# power.net
KiCad netlist of a schematic drawn in Altium Designer
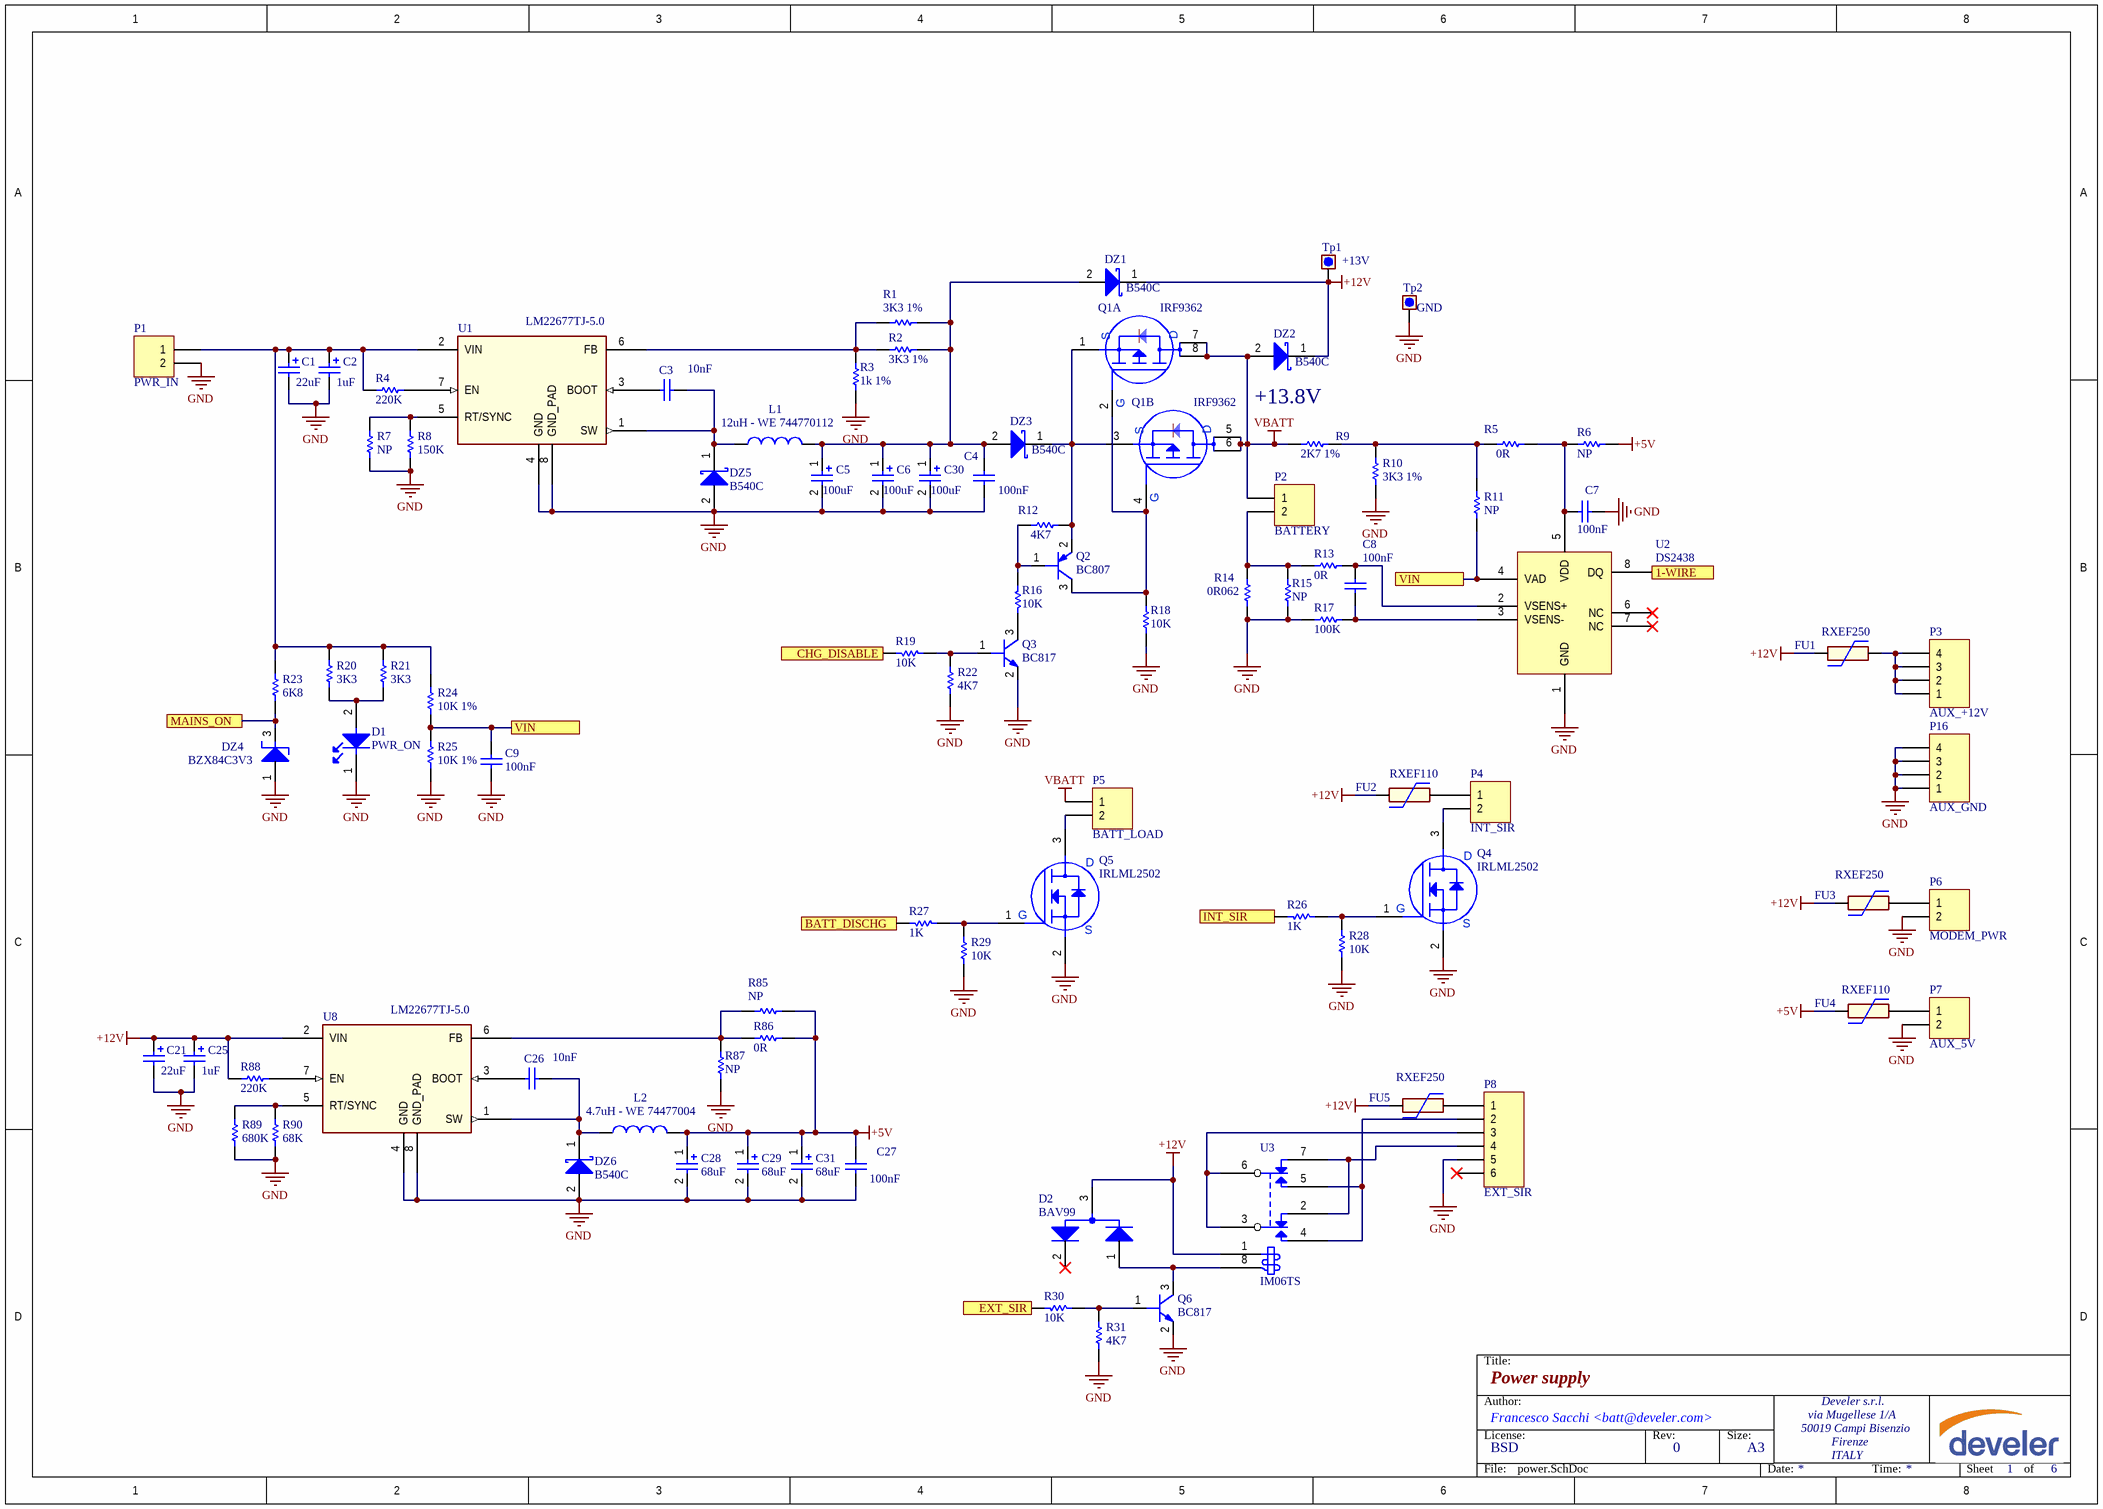
[diagram p0: power.SchDoc]

(export (version "E")
  (design (tool "Eeschema 10.0.6"))
  (components
    (comp (ref "C1")
      (value "22uF")
      (footprint "1206_[3216]")
      (description "Ceramic X7R 50V")
      (fields (field (name "PUBLISHER") "Altium Limited"))
      (libsource (lib "DEVELER_Library") (part "Cap Pol1"))
    )
    (comp (ref "C2")
      (value "1uF")
      (footprint "1206_[3216]")
      (description "Ceramic X7R 50V")
      (fields (field (name "PUBLISHER") "Altium Limited"))
      (libsource (lib "DEVELER_Library") (part "Cap Pol1"))
    )
    (comp (ref "C3")
      (value "10nF")
      (footprint "0603_[1608]")
      (description "Ceramic X7R 50V")
      (fields (field (name "PUBLISHER") "Altium Limited"))
      (libsource (lib "Miscellaneous Devices") (part "Cap"))
    )
    (comp (ref "C4")
      (value "100nF")
      (footprint "0603_[1608]")
      (description "Ceramic X7R 50V")
      (fields (field (name "PUBLISHER") "Altium Limited"))
      (libsource (lib "DEVELER_Library") (part "Cap"))
    )
    (comp (ref "C5")
      (value "100uF")
      (footprint "[7343]_CAP_TAN")
      (description "Tantalum 25V T491X107K025AT")
      (fields (field (name "PUBLISHER") "Altium Limited"))
      (libsource (lib "") (part "Cap Pol1_1"))
    )
    (comp (ref "C6")
      (value "100uF")
      (footprint "[7343]_CAP_TAN")
      (description "Tantalum 25V T491X107K025AT")
      (fields (field (name "PUBLISHER") "Altium Limited"))
      (libsource (lib "") (part "Cap Pol1_1"))
    )
    (comp (ref "C7")
      (value "100nF")
      (footprint "0603_[1608]")
      (description "Ceramic X7R 50V")
      (fields (field (name "PUBLISHER") "Altium Limited"))
      (libsource (lib "DEVELER_Library") (part "Cap"))
    )
    (comp (ref "C8")
      (value "100nF")
      (footprint "0603_[1608]")
      (description "Ceramic X7R 50V")
      (fields (field (name "PUBLISHER") "Altium Limited"))
      (libsource (lib "DEVELER_Library") (part "Cap"))
    )
    (comp (ref "C9")
      (value "100nF")
      (footprint "0603_[1608]")
      (description "Ceramic X7R 50V")
      (fields (field (name "PUBLISHER") "Altium Limited"))
      (libsource (lib "DEVELER_Library") (part "Cap"))
    )
    (comp (ref "C21")
      (value "22uF")
      (footprint "1206_[3216]")
      (description "Ceramic X7R 50V")
      (fields (field (name "PUBLISHER") "Altium Limited"))
      (libsource (lib "DEVELER_Library") (part "Cap Pol1"))
    )
    (comp (ref "C25")
      (value "1uF")
      (footprint "1206_[3216]")
      (description "Ceramic X7R 50V")
      (fields (field (name "PUBLISHER") "Altium Limited"))
      (libsource (lib "DEVELER_Library") (part "Cap Pol1"))
    )
    (comp (ref "C26")
      (value "10nF")
      (footprint "0603_[1608]")
      (description "Ceramic X7R 50V")
      (fields (field (name "PUBLISHER") "Altium Limited"))
      (libsource (lib "Miscellaneous Devices") (part "Cap"))
    )
    (comp (ref "C27")
      (value "100nF")
      (footprint "0603_[1608]")
      (description "Ceramic X7R 50V")
      (fields (field (name "PUBLISHER") "Altium Limited"))
      (libsource (lib "DEVELER_Library") (part "Cap"))
    )
    (comp (ref "C28")
      (value "68uF")
      (footprint "[7343]_CAP_TAN")
      (description "Tantalum 25V T491X107K025AT")
      (fields (field (name "PUBLISHER") "Altium Limited"))
      (libsource (lib "") (part "Cap Pol1_1"))
    )
    (comp (ref "C29")
      (value "68uF")
      (footprint "[7343]_CAP_TAN")
      (description "Tantalum 25V T491X107K025AT")
      (fields (field (name "PUBLISHER") "Altium Limited"))
      (libsource (lib "") (part "Cap Pol1_1"))
    )
    (comp (ref "C30")
      (value "100uF")
      (footprint "[7343]_CAP_TAN")
      (description "Tantalum 25V T491X107K025AT")
      (fields (field (name "PUBLISHER") "Altium Limited"))
      (libsource (lib "") (part "Cap Pol1_1"))
    )
    (comp (ref "C31")
      (value "68uF")
      (footprint "[7343]_CAP_TAN")
      (description "Tantalum 25V T491X107K025AT")
      (fields (field (name "PUBLISHER") "Altium Limited"))
      (libsource (lib "") (part "Cap Pol1_1"))
    )
    (comp (ref "D1")
      (value "PWR_ON")
      (footprint "0805_[2012]_LED")
      (description "Multicolor LED")
      (libsource (lib "DEVELER_Library") (part "LED"))
    )
    (comp (ref "D2")
      (value "BAV99")
      (footprint "SOT-23")
      (description "SOT23")
      (libsource (lib "DEVELER_Library") (part "BAV99"))
    )
    (comp (ref "DZ1")
      (value "B540C")
      (footprint "DO214AB_K1-A2_SMC")
      (description "Diode Schottky (SSC54)")
      (fields (field (name "PUBLISHER") "Altium Limited"))
      (libsource (lib "Miscellaneous Devices") (part "D Schottky"))
    )
    (comp (ref "DZ2")
      (value "B540C")
      (footprint "DO214AB_K1-A2_SMC")
      (description "Diode Schottky (SSC54)")
      (fields (field (name "PUBLISHER") "Altium Limited"))
      (libsource (lib "Miscellaneous Devices") (part "D Schottky"))
    )
    (comp (ref "DZ3")
      (value "B540C")
      (footprint "DO214AB_K1-A2_SMC")
      (description "Diode Schottky (SSC54)")
      (fields (field (name "PUBLISHER") "Altium Limited"))
      (libsource (lib "Miscellaneous Devices") (part "D Schottky"))
    )
    (comp (ref "DZ4")
      (value "BZX84C3V3")
      (footprint "SOT-23_L")
      (description "Zener 0.35W")
      (libsource (lib "DEVELER_Library") (part "ZENER_BZX"))
    )
    (comp (ref "DZ5")
      (value "B540C")
      (footprint "DO214AB_K1-A2_SMC")
      (description "Diode Schottky (SSC54)")
      (fields (field (name "PUBLISHER") "Altium Limited"))
      (libsource (lib "Miscellaneous Devices") (part "D Schottky"))
    )
    (comp (ref "DZ6")
      (value "B540C")
      (footprint "DO214AB_K1-A2_SMC")
      (description "Diode Schottky (SSC54)")
      (fields (field (name "PUBLISHER") "Altium Limited"))
      (libsource (lib "Miscellaneous Devices") (part "D Schottky"))
    )
    (comp (ref "FU1")
      (value "RXEF250")
      (footprint "RADIAL-10.2mm-polyswitch")
      (description "Fuse autoreset")
      (libsource (lib "DEVELER_Library") (part "FuseAutoReset"))
    )
    (comp (ref "FU2")
      (value "RXEF110")
      (footprint "RADIAL_5.08mm_polyswitch")
      (description "Fuse autoreset")
      (libsource (lib "DEVELER_Library") (part "FuseAutoReset"))
    )
    (comp (ref "FU3")
      (value "RXEF250")
      (footprint "RADIAL-10.2mm-polyswitch")
      (description "Fuse autoreset")
      (libsource (lib "DEVELER_Library") (part "FuseAutoReset"))
    )
    (comp (ref "FU4")
      (value "RXEF110")
      (footprint "RADIAL_5.08mm_polyswitch")
      (description "Fuse autoreset")
      (libsource (lib "DEVELER_Library") (part "FuseAutoReset"))
    )
    (comp (ref "FU5")
      (value "RXEF250")
      (footprint "RADIAL-10.2mm-polyswitch")
      (description "Fuse autoreset")
      (libsource (lib "DEVELER_Library") (part "FuseAutoReset"))
    )
    (comp (ref "L1")
      (value "12uH - WE 744770112")
      (footprint "WE-PD_1280")
      (description "SMD Shielded Tiny Power Inductor")
      (fields (field (name "PUBLISHER") "Altium Limited"))
      (libsource (lib "Miscellaneous Devices") (part "Inductor"))
    )
    (comp (ref "L2")
      (value "4.7uH - WE 74477004")
      (footprint "WE-PD_1280")
      (description "SMD Shielded Tiny Power Inductor")
      (fields (field (name "PUBLISHER") "Altium Limited"))
      (libsource (lib "Miscellaneous Devices") (part "Inductor"))
    )
    (comp (ref "P1")
      (value "PWR_IN")
      (footprint "TBLOCK_1X2_3.5MM_HOR_THD")
      (description "Header, 2-Pin")
      (fields (field (name "PUBLISHER") "Altium Limited"))
      (libsource (lib "") (part "Header 2_1"))
    )
    (comp (ref "P2")
      (value "BATTERY")
      (footprint "TBLOCK_1X2_3.5MM_HOR_THD")
      (description "Header, 2-Pin")
      (fields (field (name "PUBLISHER") "Altium Limited"))
      (libsource (lib "Miscellaneous Connectors") (part "Header 2"))
    )
    (comp (ref "P3")
      (value "AUX_+12V")
      (footprint "TBLOCK_1X4_3.5MM_HOR_THD")
      (description "Header, 4-Pin")
      (fields (field (name "PUBLISHER") "Altium Limited"))
      (libsource (lib "Miscellaneous Connectors") (part "Header 4"))
    )
    (comp (ref "P4")
      (value "INT_SIR")
      (footprint "TBLOCK_1X2_3.5MM_HOR_THD")
      (description "Header, 2-Pin")
      (fields (field (name "PUBLISHER") "Altium Limited"))
      (libsource (lib "Miscellaneous Connectors") (part "Header 2"))
    )
    (comp (ref "P5")
      (value "BATT_LOAD")
      (footprint "TBLOCK_1X2_3.5MM_HOR_THD")
      (description "Header, 2-Pin")
      (fields (field (name "PUBLISHER") "Altium Limited"))
      (libsource (lib "Miscellaneous Connectors") (part "Header 2"))
    )
    (comp (ref "P6")
      (value "MODEM_PWR")
      (footprint "TBLOCK_1X2_3.5MM_HOR_THD")
      (description "Header, 2-Pin")
      (fields (field (name "PUBLISHER") "Altium Limited"))
      (libsource (lib "Miscellaneous Connectors") (part "Header 2"))
    )
    (comp (ref "P7")
      (value "AUX_5V")
      (footprint "TBLOCK_1X2_3.5MM_HOR_THD")
      (description "Header, 2-Pin")
      (fields (field (name "PUBLISHER") "Altium Limited"))
      (libsource (lib "Miscellaneous Connectors") (part "Header 2"))
    )
    (comp (ref "P8")
      (value "EXT_SIR")
      (footprint "TBLOCK_1X6_3.5MM_HOR_THD")
      (description "Header, 6-Pin")
      (fields (field (name "PUBLISHER") "Altium Limited"))
      (libsource (lib "Miscellaneous Connectors") (part "Header 6"))
    )
    (comp (ref "P16")
      (value "AUX_GND")
      (footprint "TBLOCK_1X4_3.5MM_HOR_THD")
      (description "Header, 4-Pin")
      (fields (field (name "PUBLISHER") "Altium Limited"))
      (libsource (lib "Miscellaneous Connectors") (part "Header 4"))
    )
    (comp (ref "Q1")
      (value "IRF9362")
      (footprint "SOIC8")
      (description "Dual channel P-MOS in same package")
      (libsource (lib "DEVELER_Library") (part "MOSFET-P dual"))
    )
    (comp (ref "Q2")
      (value "BC807")
      (footprint "SOT-23")
      (description "PNP Trasistor")
      (libsource (lib "DEVELER_Library") (part "BC807"))
    )
    (comp (ref "Q3")
      (value "BC817")
      (footprint "SOT-23")
      (description "NPN Transistor")
      (libsource (lib "DEVELER_Library") (part "BC817"))
    )
    (comp (ref "Q4")
      (value "IRLML2502")
      (footprint "sot-23")
      (description "N MOS")
      (libsource (lib "DEVELER_Library") (part "MOSFET-N 3pin"))
    )
    (comp (ref "Q5")
      (value "IRLML2502")
      (footprint "sot-23")
      (description "N MOS")
      (libsource (lib "DEVELER_Library") (part "MOSFET-N 3pin"))
    )
    (comp (ref "Q6")
      (value "BC817")
      (footprint "SOT-23")
      (description "NPN Transistor")
      (libsource (lib "DEVELER_Library") (part "BC817"))
    )
    (comp (ref "R1")
      (value "3K3 1%")
      (footprint "0603_[1608]")
      (description "Resistor")
      (libsource (lib "DEVELER_Library") (part "Res1"))
    )
    (comp (ref "R2")
      (value "3K3 1%")
      (footprint "0603_[1608]")
      (description "Resistor")
      (libsource (lib "DEVELER_Library") (part "Res1"))
    )
    (comp (ref "R3")
      (value "1k 1%")
      (footprint "0603_[1608]")
      (description "Resistor")
      (libsource (lib "DEVELER_Library") (part "Res1"))
    )
    (comp (ref "R4")
      (value "220K")
      (footprint "0603_[1608]")
      (description "Resistor")
      (libsource (lib "DEVELER_Library") (part "Res1"))
    )
    (comp (ref "R5")
      (value "0R")
      (footprint "0603_[1608]")
      (description "Resistor")
      (libsource (lib "DEVELER_Library") (part "Res1"))
    )
    (comp (ref "R6")
      (value "NP")
      (footprint "0603_[1608]")
      (description "Resistor")
      (libsource (lib "DEVELER_Library") (part "Res1"))
    )
    (comp (ref "R7")
      (value "NP")
      (footprint "0603_[1608]")
      (description "Resistor")
      (libsource (lib "DEVELER_Library") (part "Res1"))
    )
    (comp (ref "R8")
      (value "150K")
      (footprint "0603_[1608]")
      (description "Resistor")
      (libsource (lib "DEVELER_Library") (part "Res1"))
    )
    (comp (ref "R9")
      (value "2K7 1%")
      (footprint "0603_[1608]")
      (description "Resistor")
      (libsource (lib "DEVELER_Library") (part "Res1"))
    )
    (comp (ref "R10")
      (value "3K3 1%")
      (footprint "0603_[1608]")
      (description "Resistor")
      (libsource (lib "DEVELER_Library") (part "Res1"))
    )
    (comp (ref "R11")
      (value "NP")
      (footprint "0603_[1608]")
      (description "Resistor")
      (libsource (lib "DEVELER_Library") (part "Res1"))
    )
    (comp (ref "R12")
      (value "4K7")
      (footprint "0603_[1608]")
      (description "Resistor")
      (libsource (lib "DEVELER_Library") (part "Res1"))
    )
    (comp (ref "R13")
      (value "0R")
      (footprint "0603_[1608]")
      (description "Resistor")
      (libsource (lib "DEVELER_Library") (part "Res1"))
    )
    (comp (ref "R14")
      (value "0R062")
      (footprint "1020_[2550]")
      (description "Resistor")
      (libsource (lib "DEVELER_Library") (part "Res1"))
    )
    (comp (ref "R15")
      (value "NP")
      (footprint "0603_[1608]")
      (description "Resistor")
      (libsource (lib "DEVELER_Library") (part "Res1"))
    )
    (comp (ref "R16")
      (value "10K")
      (footprint "0603_[1608]")
      (description "Resistor")
      (libsource (lib "DEVELER_Library") (part "Res1"))
    )
    (comp (ref "R17")
      (value "100K")
      (footprint "0603_[1608]")
      (description "Resistor")
      (libsource (lib "DEVELER_Library") (part "Res1"))
    )
    (comp (ref "R18")
      (value "10K")
      (footprint "0603_[1608]")
      (description "Resistor")
      (libsource (lib "DEVELER_Library") (part "Res1"))
    )
    (comp (ref "R19")
      (value "10K")
      (footprint "0603_[1608]")
      (description "Resistor")
      (libsource (lib "DEVELER_Library") (part "Res1"))
    )
    (comp (ref "R20")
      (value "3K3")
      (footprint "0603_[1608]")
      (description "Resistor")
      (libsource (lib "DEVELER_Library") (part "Res1"))
    )
    (comp (ref "R21")
      (value "3K3")
      (footprint "0603_[1608]")
      (description "Resistor")
      (libsource (lib "DEVELER_Library") (part "Res1"))
    )
    (comp (ref "R22")
      (value "4K7")
      (footprint "0603_[1608]")
      (description "Resistor")
      (libsource (lib "DEVELER_Library") (part "Res1"))
    )
    (comp (ref "R23")
      (value "6K8")
      (footprint "0603_[1608]")
      (description "Resistor")
      (libsource (lib "DEVELER_Library") (part "Res1"))
    )
    (comp (ref "R24")
      (value "10K 1%")
      (footprint "0603_[1608]")
      (description "Resistor")
      (libsource (lib "DEVELER_Library") (part "Res1"))
    )
    (comp (ref "R25")
      (value "10K 1%")
      (footprint "0603_[1608]")
      (description "Resistor")
      (libsource (lib "DEVELER_Library") (part "Res1"))
    )
    (comp (ref "R26")
      (value "1K")
      (footprint "0603_[1608]")
      (description "Resistor")
      (libsource (lib "DEVELER_Library") (part "Res1"))
    )
    (comp (ref "R27")
      (value "1K")
      (footprint "0603_[1608]")
      (description "Resistor")
      (libsource (lib "DEVELER_Library") (part "Res1"))
    )
    (comp (ref "R28")
      (value "10K")
      (footprint "0603_[1608]")
      (description "Resistor")
      (libsource (lib "DEVELER_Library") (part "Res1"))
    )
    (comp (ref "R29")
      (value "10K")
      (footprint "0603_[1608]")
      (description "Resistor")
      (libsource (lib "DEVELER_Library") (part "Res1"))
    )
    (comp (ref "R30")
      (value "10K")
      (footprint "0603_[1608]")
      (description "Resistor")
      (libsource (lib "DEVELER_Library") (part "Res1"))
    )
    (comp (ref "R31")
      (value "4K7")
      (footprint "0603_[1608]")
      (description "Resistor")
      (libsource (lib "DEVELER_Library") (part "Res1"))
    )
    (comp (ref "R85")
      (value "NP")
      (footprint "0603_[1608]")
      (description "Resistor")
      (libsource (lib "DEVELER_Library") (part "Res1"))
    )
    (comp (ref "R86")
      (value "0R")
      (footprint "0603_[1608]")
      (description "Resistor")
      (libsource (lib "DEVELER_Library") (part "Res1"))
    )
    (comp (ref "R87")
      (value "NP")
      (footprint "0603_[1608]")
      (description "Resistor")
      (libsource (lib "DEVELER_Library") (part "Res1"))
    )
    (comp (ref "R88")
      (value "220K")
      (footprint "0603_[1608]")
      (description "Resistor")
      (libsource (lib "DEVELER_Library") (part "Res1"))
    )
    (comp (ref "R89")
      (value "680K")
      (footprint "0603_[1608]")
      (description "Resistor")
      (libsource (lib "DEVELER_Library") (part "Res1"))
    )
    (comp (ref "R90")
      (value "68K")
      (footprint "0603_[1608]")
      (description "Resistor")
      (libsource (lib "DEVELER_Library") (part "Res1"))
    )
    (comp (ref "Tp1")
      (value "+13V")
      (footprint "TEST_POINT_THD_D1.6MM")
      (libsource (lib "DEVELER_Library") (part "Test_point"))
    )
    (comp (ref "Tp2")
      (value "GND")
      (footprint "TEST_POINT_THD_D1.6MM")
      (libsource (lib "DEVELER_Library") (part "Test_point"))
    )
    (comp (ref "U1")
      (value "LM22677TJ-5.0")
      (footprint "TO-263-7")
      (description "Switching regulator.")
      (libsource (lib "DEVELER_Library") (part "LM22670TJ-ADJ"))
    )
    (comp (ref "U2")
      (value "DS2438")
      (footprint "SOIC8")
      (description "Smart Battery Monitor")
      (libsource (lib "DEVELER_Library") (part "DS2438"))
    )
    (comp (ref "U3")
      (value "IM06TS")
      (footprint "RELAYS_DPST_THD_6x10_3.2mm")
      (description "Relay DPST")
      (libsource (lib "DEVELER_Library") (part "RELAY DPST"))
    )
    (comp (ref "U8")
      (value "LM22677TJ-5.0")
      (footprint "TO-263-7")
      (description "Switching regulator.")
      (libsource (lib "DEVELER_Library") (part "LM22670TJ-ADJ"))
    )
  )
  (nets
    (net (code "1") (name "+5V") (class "Default")
      (node (ref "C27") (pin "2") (pinfunction "2_2") (pintype "passive"))
      (node (ref "C28") (pin "1") (pinfunction "1_1") (pintype "passive"))
      (node (ref "C29") (pin "1") (pinfunction "1_1") (pintype "passive"))
      (node (ref "C31") (pin "1") (pinfunction "1_1") (pintype "passive"))
      (node (ref "FU4") (pin "1") (pinfunction "1_1") (pintype "passive"))
      (node (ref "L2") (pin "2") (pinfunction "2_2") (pintype "passive"))
      (node (ref "R6") (pin "1") (pinfunction "1_1") (pintype "passive"))
      (node (ref "R85") (pin "1") (pinfunction "1_1") (pintype "passive"))
      (node (ref "R86") (pin "1") (pinfunction "1_1") (pintype "passive"))
    )
    (net (code "2") (name "+12V") (class "Default")
      (node (ref "C21") (pin "1") (pinfunction "1_1") (pintype "passive"))
      (node (ref "C25") (pin "1") (pinfunction "1_1") (pintype "passive"))
      (node (ref "D2") (pin "3") (pinfunction "3_3") (pintype "passive"))
      (node (ref "DZ1") (pin "1") (pinfunction "K_1") (pintype "passive"))
      (node (ref "DZ2") (pin "1") (pinfunction "K_1") (pintype "passive"))
      (node (ref "FU1") (pin "1") (pinfunction "1_1") (pintype "passive"))
      (node (ref "FU2") (pin "1") (pinfunction "1_1") (pintype "passive"))
      (node (ref "FU3") (pin "1") (pinfunction "1_1") (pintype "passive"))
      (node (ref "FU5") (pin "1") (pinfunction "1_1") (pintype "passive"))
      (node (ref "R88") (pin "1") (pinfunction "1_1") (pintype "passive"))
      (node (ref "Tp1") (pin "1") (pinfunction "1_1") (pintype "passive"))
      (node (ref "U3") (pin "1") (pinfunction "1_1") (pintype "passive"))
      (node (ref "U8") (pin "2") (pinfunction "VIN_2") (pintype "power_in"))
    )
    (net (code "3") (name "/1-WIRE") (class "Default")
      (node (ref "U2") (pin "8") (pinfunction "DQ_8") (pintype "passive"))
    )
    (net (code "4") (name "/BATT_DISCHG") (class "Default")
      (node (ref "R27") (pin "1") (pinfunction "1_1") (pintype "passive"))
    )
    (net (code "5") (name "/CHG_DISABLE") (class "Default")
      (node (ref "R19") (pin "1") (pinfunction "1_1") (pintype "passive"))
    )
    (net (code "6") (name "/EXT_SIR") (class "Default")
      (node (ref "R30") (pin "1") (pinfunction "1_1") (pintype "passive"))
    )
    (net (code "7") (name "/INT_SIR") (class "Default")
      (node (ref "R26") (pin "1") (pinfunction "1_1") (pintype "passive"))
    )
    (net (code "8") (name "/MAINS_ON") (class "Default")
      (node (ref "DZ4") (pin "3") (pinfunction "K_3") (pintype "passive"))
      (node (ref "R23") (pin "1") (pinfunction "1_1") (pintype "passive"))
    )
    (net (code "9") (name "/VIN") (class "Default")
      (node (ref "C9") (pin "2") (pinfunction "2_2") (pintype "passive"))
      (node (ref "R11") (pin "1") (pinfunction "1_1") (pintype "passive"))
      (node (ref "R24") (pin "1") (pinfunction "1_1") (pintype "passive"))
      (node (ref "R25") (pin "2") (pinfunction "2_2") (pintype "passive"))
      (node (ref "U2") (pin "4") (pinfunction "VAD_4") (pintype "passive"))
    )
    (net (code "10") (name "GND") (class "Default")
      (node (ref "C1") (pin "2") (pinfunction "2_2") (pintype "passive"))
      (node (ref "C2") (pin "2") (pinfunction "2_2") (pintype "passive"))
      (node (ref "C21") (pin "2") (pinfunction "2_2") (pintype "passive"))
      (node (ref "C25") (pin "2") (pinfunction "2_2") (pintype "passive"))
      (node (ref "C27") (pin "1") (pinfunction "1_1") (pintype "passive"))
      (node (ref "C28") (pin "2") (pinfunction "2_2") (pintype "passive"))
      (node (ref "C29") (pin "2") (pinfunction "2_2") (pintype "passive"))
      (node (ref "C30") (pin "2") (pinfunction "2_2") (pintype "passive"))
      (node (ref "C31") (pin "2") (pinfunction "2_2") (pintype "passive"))
      (node (ref "C4") (pin "1") (pinfunction "1_1") (pintype "passive"))
      (node (ref "C5") (pin "2") (pinfunction "2_2") (pintype "passive"))
      (node (ref "C6") (pin "2") (pinfunction "2_2") (pintype "passive"))
      (node (ref "C7") (pin "1") (pinfunction "1_1") (pintype "passive"))
      (node (ref "C9") (pin "1") (pinfunction "1_1") (pintype "passive"))
      (node (ref "D1") (pin "1") (pinfunction "K_1") (pintype "passive"))
      (node (ref "DZ4") (pin "1") (pinfunction "A_1") (pintype "passive"))
      (node (ref "DZ5") (pin "2") (pinfunction "A_2") (pintype "passive"))
      (node (ref "DZ6") (pin "2") (pinfunction "A_2") (pintype "passive"))
      (node (ref "P1") (pin "2") (pinfunction "2_2") (pintype "passive"))
      (node (ref "P16") (pin "1") (pinfunction "1_1") (pintype "passive"))
      (node (ref "P16") (pin "2") (pinfunction "2_2") (pintype "passive"))
      (node (ref "P16") (pin "3") (pinfunction "3_3") (pintype "passive"))
      (node (ref "P16") (pin "4") (pinfunction "4_4") (pintype "passive"))
      (node (ref "P6") (pin "2") (pinfunction "2_2") (pintype "passive"))
      (node (ref "P7") (pin "2") (pinfunction "2_2") (pintype "passive"))
      (node (ref "P8") (pin "5") (pinfunction "5_5") (pintype "passive"))
      (node (ref "Q3") (pin "2") (pinfunction "E_2") (pintype "passive"))
      (node (ref "Q4") (pin "2") (pinfunction "S_2") (pintype "passive"))
      (node (ref "Q5") (pin "2") (pinfunction "S_2") (pintype "passive"))
      (node (ref "Q6") (pin "2") (pinfunction "E_2") (pintype "passive"))
      (node (ref "R10") (pin "1") (pinfunction "1_1") (pintype "passive"))
      (node (ref "R14") (pin "2") (pinfunction "2_2") (pintype "passive"))
      (node (ref "R15") (pin "2") (pinfunction "2_2") (pintype "passive"))
      (node (ref "R17") (pin "1") (pinfunction "1_1") (pintype "passive"))
      (node (ref "R18") (pin "1") (pinfunction "1_1") (pintype "passive"))
      (node (ref "R22") (pin "1") (pinfunction "1_1") (pintype "passive"))
      (node (ref "R25") (pin "1") (pinfunction "1_1") (pintype "passive"))
      (node (ref "R28") (pin "1") (pinfunction "1_1") (pintype "passive"))
      (node (ref "R29") (pin "1") (pinfunction "1_1") (pintype "passive"))
      (node (ref "R3") (pin "2") (pinfunction "2_2") (pintype "passive"))
      (node (ref "R31") (pin "1") (pinfunction "1_1") (pintype "passive"))
      (node (ref "R7") (pin "1") (pinfunction "1_1") (pintype "passive"))
      (node (ref "R8") (pin "1") (pinfunction "1_1") (pintype "passive"))
      (node (ref "R87") (pin "2") (pinfunction "2_2") (pintype "passive"))
      (node (ref "R89") (pin "1") (pinfunction "1_1") (pintype "passive"))
      (node (ref "R90") (pin "1") (pinfunction "1_1") (pintype "passive"))
      (node (ref "Tp2") (pin "1") (pinfunction "1_1") (pintype "passive"))
      (node (ref "U1") (pin "4") (pinfunction "GND_4") (pintype "power_in"))
      (node (ref "U1") (pin "8") (pinfunction "GND_PAD_8") (pintype "power_in"))
      (node (ref "U2") (pin "1") (pinfunction "GND_1") (pintype "power_in"))
      (node (ref "U8") (pin "4") (pinfunction "GND_4") (pintype "power_in"))
      (node (ref "U8") (pin "8") (pinfunction "GND_PAD_8") (pintype "power_in"))
    )
    (net (code "11") (name "Net-(D1-A)") (class "Default")
      (node (ref "D1") (pin "2") (pinfunction "A_2") (pintype "passive"))
      (node (ref "R20") (pin "1") (pinfunction "1_1") (pintype "passive"))
      (node (ref "R21") (pin "1") (pinfunction "1_1") (pintype "passive"))
    )
    (net (code "12") (name "Net-(DZ1-A)") (class "Default")
      (node (ref "C30") (pin "1") (pinfunction "1_1") (pintype "passive"))
      (node (ref "C4") (pin "2") (pinfunction "2_2") (pintype "passive"))
      (node (ref "C5") (pin "1") (pinfunction "1_1") (pintype "passive"))
      (node (ref "C6") (pin "1") (pinfunction "1_1") (pintype "passive"))
      (node (ref "DZ1") (pin "2") (pinfunction "A_2") (pintype "passive"))
      (node (ref "DZ3") (pin "2") (pinfunction "A_2") (pintype "passive"))
      (node (ref "L1") (pin "2") (pinfunction "2_2") (pintype "passive"))
      (node (ref "R1") (pin "1") (pinfunction "1_1") (pintype "passive"))
      (node (ref "R2") (pin "1") (pinfunction "1_1") (pintype "passive"))
    )
    (net (code "13") (name "Net-(DZ3-K)") (class "Default")
      (node (ref "DZ3") (pin "1") (pinfunction "K_1") (pintype "passive"))
      (node (ref "Q1") (pin "1") (pinfunction "S_1") (pintype "passive"))
      (node (ref "Q1") (pin "3") (pinfunction "S_3") (pintype "passive"))
      (node (ref "Q2") (pin "2") (pinfunction "E_2") (pintype "passive"))
      (node (ref "R12") (pin "2") (pinfunction "2_2") (pintype "passive"))
    )
    (net (code "14") (name "Net-(DZ5-K)") (class "Default")
      (node (ref "C3") (pin "2") (pinfunction "2_2") (pintype "passive"))
      (node (ref "DZ5") (pin "1") (pinfunction "K_1") (pintype "passive"))
      (node (ref "L1") (pin "1") (pinfunction "1_1") (pintype "passive"))
      (node (ref "U1") (pin "1") (pinfunction "SW_1") (pintype "output"))
    )
    (net (code "15") (name "Net-(DZ6-K)") (class "Default")
      (node (ref "C26") (pin "2") (pinfunction "2_2") (pintype "passive"))
      (node (ref "DZ6") (pin "1") (pinfunction "K_1") (pintype "passive"))
      (node (ref "L2") (pin "1") (pinfunction "1_1") (pintype "passive"))
      (node (ref "U8") (pin "1") (pinfunction "SW_1") (pintype "output"))
    )
    (net (code "16") (name "Net-(FU1-Pad2)") (class "Default")
      (node (ref "FU1") (pin "2") (pinfunction "2_2") (pintype "passive"))
      (node (ref "P3") (pin "1") (pinfunction "1_1") (pintype "passive"))
      (node (ref "P3") (pin "2") (pinfunction "2_2") (pintype "passive"))
      (node (ref "P3") (pin "3") (pinfunction "3_3") (pintype "passive"))
      (node (ref "P3") (pin "4") (pinfunction "4_4") (pintype "passive"))
    )
    (net (code "17") (name "Net-(FU2-Pad2)") (class "Default")
      (node (ref "FU2") (pin "2") (pinfunction "2_2") (pintype "passive"))
      (node (ref "P4") (pin "1") (pinfunction "1_1") (pintype "passive"))
    )
    (net (code "18") (name "Net-(FU3-Pad2)") (class "Default")
      (node (ref "FU3") (pin "2") (pinfunction "2_2") (pintype "passive"))
      (node (ref "P6") (pin "1") (pinfunction "1_1") (pintype "passive"))
    )
    (net (code "19") (name "Net-(FU4-Pad2)") (class "Default")
      (node (ref "FU4") (pin "2") (pinfunction "2_2") (pintype "passive"))
      (node (ref "P7") (pin "1") (pinfunction "1_1") (pintype "passive"))
    )
    (net (code "20") (name "Net-(FU5-Pad2)") (class "Default")
      (node (ref "FU5") (pin "2") (pinfunction "2_2") (pintype "passive"))
      (node (ref "P8") (pin "1") (pinfunction "1_1") (pintype "passive"))
    )
    (net (code "21") (name "Net-(P2-Pad2)") (class "Default")
      (node (ref "P2") (pin "2") (pinfunction "2_2") (pintype "passive"))
      (node (ref "R13") (pin "1") (pinfunction "1_1") (pintype "passive"))
      (node (ref "R14") (pin "1") (pinfunction "1_1") (pintype "passive"))
      (node (ref "R15") (pin "1") (pinfunction "1_1") (pintype "passive"))
    )
    (net (code "22") (name "Net-(P8-Pad2)") (class "Default")
      (node (ref "P8") (pin "2") (pinfunction "2_2") (pintype "passive"))
      (node (ref "U3") (pin "4") (pinfunction "4_4") (pintype "passive"))
      (node (ref "U3") (pin "5") (pinfunction "5_5") (pintype "passive"))
    )
    (net (code "23") (name "Net-(P8-Pad3)") (class "Default")
      (node (ref "P8") (pin "3") (pinfunction "3_3") (pintype "passive"))
      (node (ref "U3") (pin "3") (pinfunction "3_3") (pintype "passive"))
      (node (ref "U3") (pin "6") (pinfunction "6_6") (pintype "passive"))
    )
    (net (code "24") (name "Net-(P8-Pad4)") (class "Default")
      (node (ref "P8") (pin "4") (pinfunction "4_4") (pintype "passive"))
      (node (ref "U3") (pin "2") (pinfunction "2_2") (pintype "passive"))
      (node (ref "U3") (pin "7") (pinfunction "7_7") (pintype "passive"))
    )
    (net (code "25") (name "Net-(Q1A-G)") (class "Default")
      (node (ref "Q1") (pin "2") (pinfunction "G_2") (pintype "passive"))
      (node (ref "Q1") (pin "4") (pinfunction "G_4") (pintype "passive"))
      (node (ref "Q2") (pin "3") (pinfunction "C_3") (pintype "passive"))
      (node (ref "R18") (pin "2") (pinfunction "2_2") (pintype "passive"))
    )
    (net (code "26") (name "Net-(Q2-B)") (class "Default")
      (node (ref "Q2") (pin "1") (pinfunction "B_1") (pintype "passive"))
      (node (ref "R12") (pin "1") (pinfunction "1_1") (pintype "passive"))
      (node (ref "R16") (pin "2") (pinfunction "2_2") (pintype "passive"))
    )
    (net (code "27") (name "Net-(Q3-B)") (class "Default")
      (node (ref "Q3") (pin "1") (pinfunction "B_1") (pintype "passive"))
      (node (ref "R19") (pin "2") (pinfunction "2_2") (pintype "passive"))
      (node (ref "R22") (pin "2") (pinfunction "2_2") (pintype "passive"))
    )
    (net (code "28") (name "Net-(Q3-C)") (class "Default")
      (node (ref "Q3") (pin "3") (pinfunction "C_3") (pintype "passive"))
      (node (ref "R16") (pin "1") (pinfunction "1_1") (pintype "passive"))
    )
    (net (code "29") (name "Net-(Q4-D)") (class "Default")
      (node (ref "P4") (pin "2") (pinfunction "2_2") (pintype "passive"))
      (node (ref "Q4") (pin "3") (pinfunction "D_3") (pintype "passive"))
    )
    (net (code "30") (name "Net-(Q4-G)") (class "Default")
      (node (ref "Q4") (pin "1") (pinfunction "G_1") (pintype "passive"))
      (node (ref "R26") (pin "2") (pinfunction "2_2") (pintype "passive"))
      (node (ref "R28") (pin "2") (pinfunction "2_2") (pintype "passive"))
    )
    (net (code "31") (name "Net-(Q5-D)") (class "Default")
      (node (ref "P5") (pin "2") (pinfunction "2_2") (pintype "passive"))
      (node (ref "Q5") (pin "3") (pinfunction "D_3") (pintype "passive"))
    )
    (net (code "32") (name "Net-(Q5-G)") (class "Default")
      (node (ref "Q5") (pin "1") (pinfunction "G_1") (pintype "passive"))
      (node (ref "R27") (pin "2") (pinfunction "2_2") (pintype "passive"))
      (node (ref "R29") (pin "2") (pinfunction "2_2") (pintype "passive"))
    )
    (net (code "33") (name "Net-(Q6-B)") (class "Default")
      (node (ref "Q6") (pin "1") (pinfunction "B_1") (pintype "passive"))
      (node (ref "R30") (pin "2") (pinfunction "2_2") (pintype "passive"))
      (node (ref "R31") (pin "2") (pinfunction "2_2") (pintype "passive"))
    )
    (net (code "34") (name "Net-(Q6-C)") (class "Default")
      (node (ref "D2") (pin "1") (pinfunction "1_1") (pintype "passive"))
      (node (ref "Q6") (pin "3") (pinfunction "C_3") (pintype "passive"))
      (node (ref "U3") (pin "8") (pinfunction "8_8") (pintype "passive"))
    )
    (net (code "35") (name "Net-(R10-Pad2)") (class "Default")
      (node (ref "R10") (pin "2") (pinfunction "2_2") (pintype "passive"))
      (node (ref "R11") (pin "2") (pinfunction "2_2") (pintype "passive"))
      (node (ref "R5") (pin "2") (pinfunction "2_2") (pintype "passive"))
      (node (ref "R9") (pin "1") (pinfunction "1_1") (pintype "passive"))
    )
    (net (code "36") (name "Net-(U1-BOOT)") (class "Default")
      (node (ref "C3") (pin "1") (pinfunction "1_1") (pintype "passive"))
      (node (ref "U1") (pin "3") (pinfunction "BOOT_3") (pintype "input"))
    )
    (net (code "37") (name "Net-(U1-EN)") (class "Default")
      (node (ref "R4") (pin "2") (pinfunction "2_2") (pintype "passive"))
      (node (ref "U1") (pin "7") (pinfunction "EN_7") (pintype "input"))
    )
    (net (code "38") (name "Net-(U1-FB)") (class "Default")
      (node (ref "R1") (pin "2") (pinfunction "2_2") (pintype "passive"))
      (node (ref "R2") (pin "2") (pinfunction "2_2") (pintype "passive"))
      (node (ref "R3") (pin "1") (pinfunction "1_1") (pintype "passive"))
      (node (ref "U1") (pin "6") (pinfunction "FB_6") (pintype "passive"))
    )
    (net (code "39") (name "Net-(U1-RT{slash}SYNC)") (class "Default")
      (node (ref "R7") (pin "2") (pinfunction "2_2") (pintype "passive"))
      (node (ref "R8") (pin "2") (pinfunction "2_2") (pintype "passive"))
      (node (ref "U1") (pin "5") (pinfunction "RT/SYNC_5") (pintype "passive"))
    )
    (net (code "40") (name "Net-(U1-VIN)") (class "Default")
      (node (ref "C1") (pin "1") (pinfunction "1_1") (pintype "passive"))
      (node (ref "C2") (pin "1") (pinfunction "1_1") (pintype "passive"))
      (node (ref "P1") (pin "1") (pinfunction "1_1") (pintype "passive"))
      (node (ref "R20") (pin "2") (pinfunction "2_2") (pintype "passive"))
      (node (ref "R21") (pin "2") (pinfunction "2_2") (pintype "passive"))
      (node (ref "R23") (pin "2") (pinfunction "2_2") (pintype "passive"))
      (node (ref "R24") (pin "2") (pinfunction "2_2") (pintype "passive"))
      (node (ref "R4") (pin "1") (pinfunction "1_1") (pintype "passive"))
      (node (ref "U1") (pin "2") (pinfunction "VIN_2") (pintype "power_in"))
    )
    (net (code "41") (name "Net-(U2-VDD)") (class "Default")
      (node (ref "C7") (pin "2") (pinfunction "2_2") (pintype "passive"))
      (node (ref "R5") (pin "1") (pinfunction "1_1") (pintype "passive"))
      (node (ref "R6") (pin "2") (pinfunction "2_2") (pintype "passive"))
      (node (ref "U2") (pin "5") (pinfunction "VDD_5") (pintype "power_in"))
    )
    (net (code "42") (name "Net-(U2-VSENS+)") (class "Default")
      (node (ref "C8") (pin "2") (pinfunction "2_2") (pintype "passive"))
      (node (ref "R13") (pin "2") (pinfunction "2_2") (pintype "passive"))
      (node (ref "U2") (pin "2") (pinfunction "VSENS+_2") (pintype "passive"))
    )
    (net (code "43") (name "Net-(U2-VSENS-)") (class "Default")
      (node (ref "C8") (pin "1") (pinfunction "1_1") (pintype "passive"))
      (node (ref "R17") (pin "2") (pinfunction "2_2") (pintype "passive"))
      (node (ref "U2") (pin "3") (pinfunction "VSENS-_3") (pintype "passive"))
    )
    (net (code "44") (name "Net-(U8-BOOT)") (class "Default")
      (node (ref "C26") (pin "1") (pinfunction "1_1") (pintype "passive"))
      (node (ref "U8") (pin "3") (pinfunction "BOOT_3") (pintype "input"))
    )
    (net (code "45") (name "Net-(U8-EN)") (class "Default")
      (node (ref "R88") (pin "2") (pinfunction "2_2") (pintype "passive"))
      (node (ref "U8") (pin "7") (pinfunction "EN_7") (pintype "input"))
    )
    (net (code "46") (name "Net-(U8-FB)") (class "Default")
      (node (ref "R85") (pin "2") (pinfunction "2_2") (pintype "passive"))
      (node (ref "R86") (pin "2") (pinfunction "2_2") (pintype "passive"))
      (node (ref "R87") (pin "1") (pinfunction "1_1") (pintype "passive"))
      (node (ref "U8") (pin "6") (pinfunction "FB_6") (pintype "passive"))
    )
    (net (code "47") (name "Net-(U8-RT{slash}SYNC)") (class "Default")
      (node (ref "R89") (pin "2") (pinfunction "2_2") (pintype "passive"))
      (node (ref "R90") (pin "2") (pinfunction "2_2") (pintype "passive"))
      (node (ref "U8") (pin "5") (pinfunction "RT/SYNC_5") (pintype "passive"))
    )
    (net (code "48") (name "VBATT") (class "Default")
      (node (ref "DZ2") (pin "2") (pinfunction "A_2") (pintype "passive"))
      (node (ref "P2") (pin "1") (pinfunction "1_1") (pintype "passive"))
      (node (ref "P5") (pin "1") (pinfunction "1_1") (pintype "passive"))
      (node (ref "Q1") (pin "5") (pinfunction "D_5") (pintype "passive"))
      (node (ref "Q1") (pin "6") (pinfunction "D_6") (pintype "passive"))
      (node (ref "Q1") (pin "7") (pinfunction "D_7") (pintype "passive"))
      (node (ref "Q1") (pin "8") (pinfunction "D_8") (pintype "passive"))
      (node (ref "R9") (pin "2") (pinfunction "2_2") (pintype "passive"))
    )
    (net (code "49") (name "unconnected-(D2-Pad2)") (class "Default")
      (node (ref "D2") (pin "2") (pinfunction "2_2") (pintype "passive+no_connect"))
    )
    (net (code "50") (name "unconnected-(P8-Pad6)") (class "Default")
      (node (ref "P8") (pin "6") (pinfunction "6_6") (pintype "passive+no_connect"))
    )
    (net (code "51") (name "unconnected-(U2-NC-Pad6)") (class "Default")
      (node (ref "U2") (pin "6") (pinfunction "NC_6") (pintype "passive+no_connect"))
    )
    (net (code "52") (name "unconnected-(U2-NC-Pad7)") (class "Default")
      (node (ref "U2") (pin "7") (pinfunction "NC_7") (pintype "passive+no_connect"))
    )
  )
)
